# sismin_LC.net
KiCad netlist of a schematic drawn in EAGLE
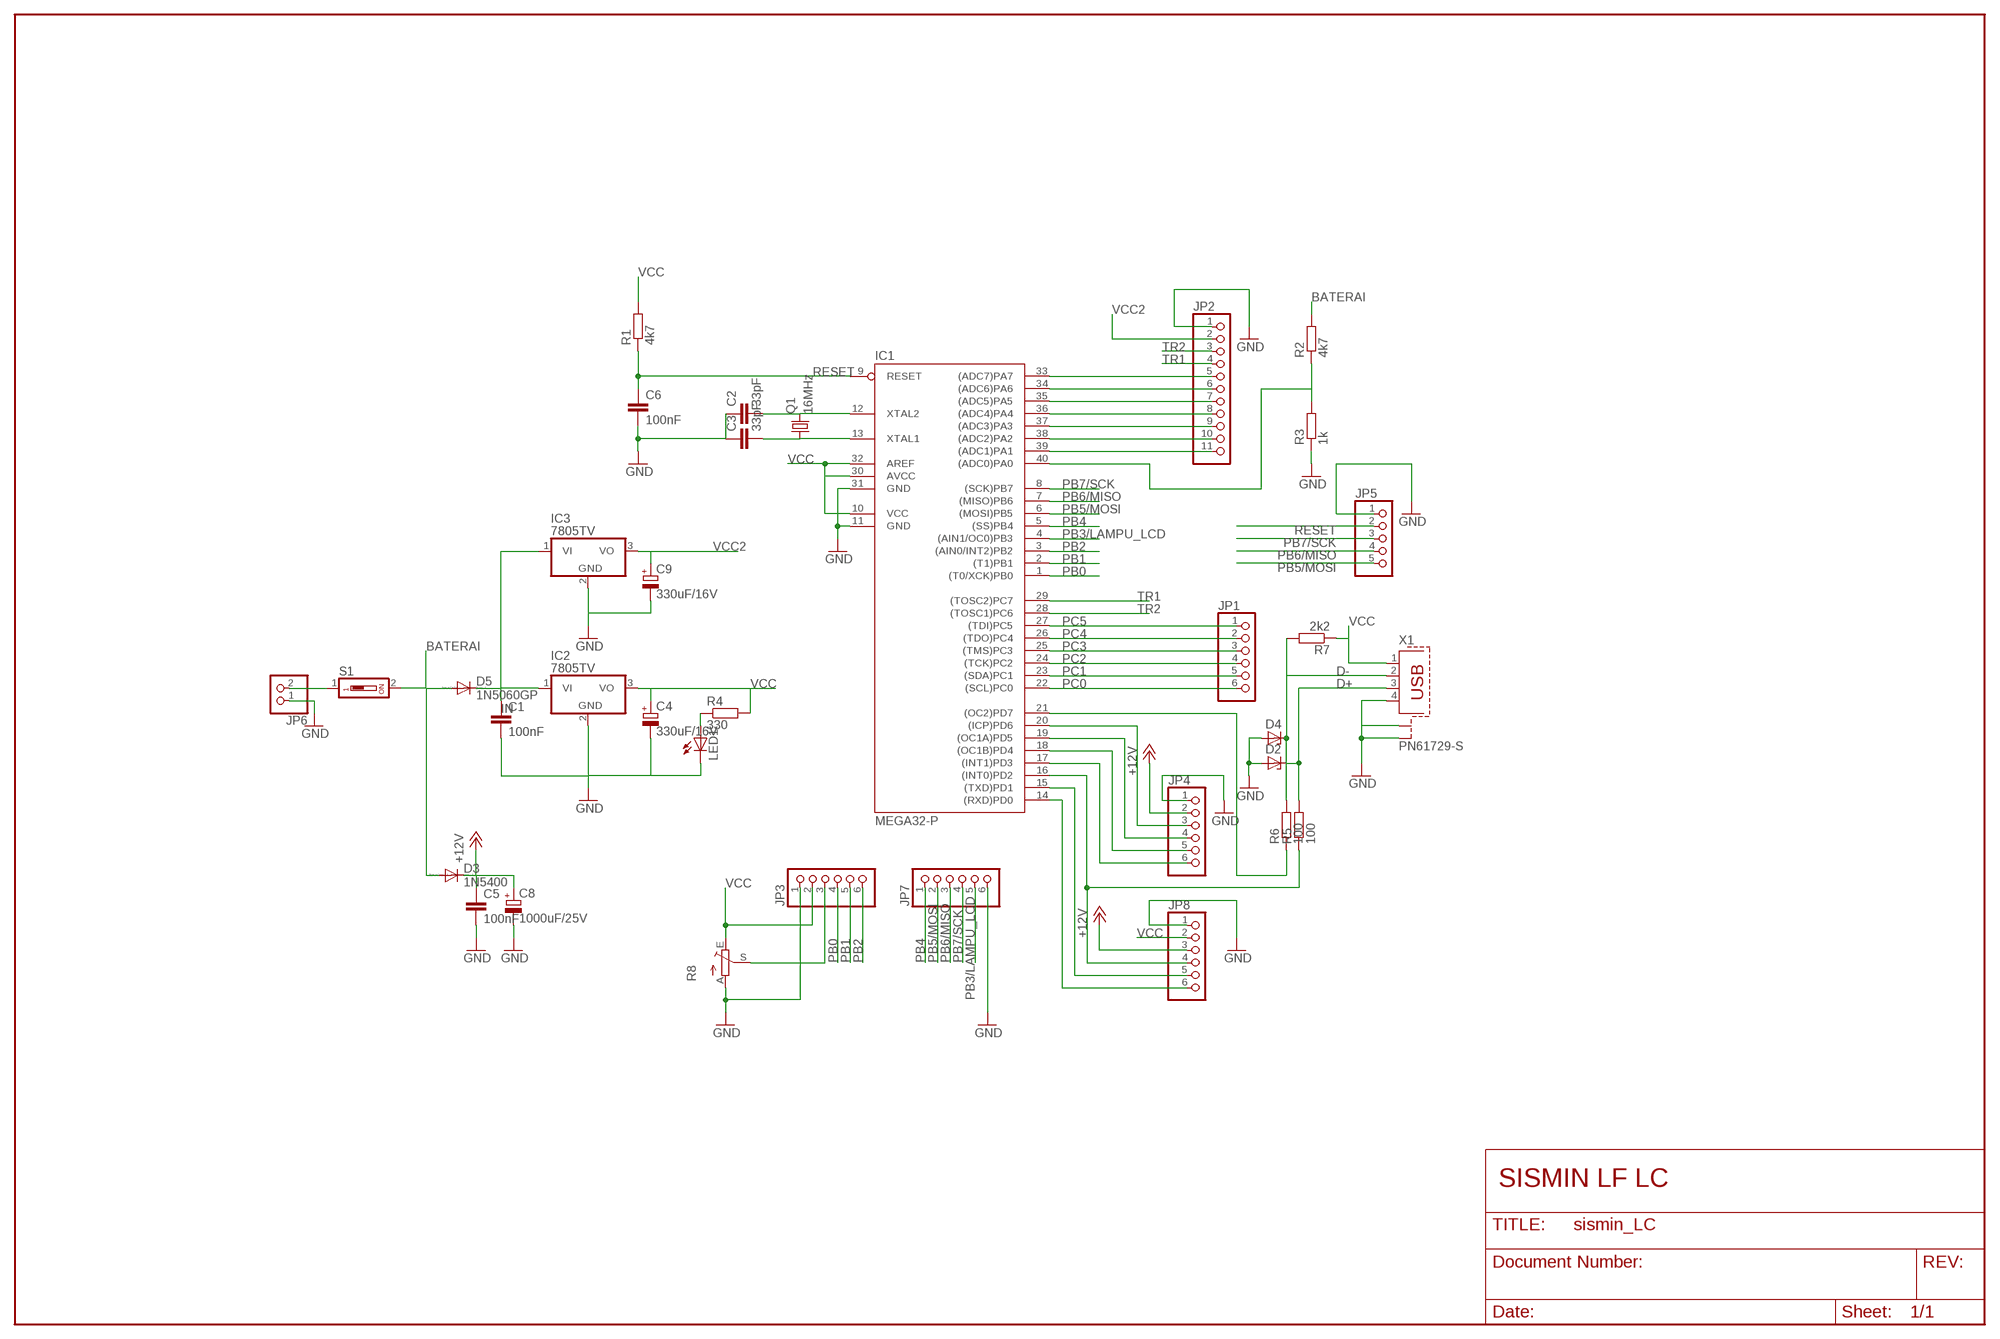
[diagram p0: schematic, sheet 1]

(export (version "E")
  (design (tool "Eeschema 10.0.6"))
  (components
    (comp (ref "C1")
      (value "100nF")
      (footprint "eagle-import:C050-025X075")
      (libsource (lib "eagle-import") (part "C-EU050-025X075"))
    )
    (comp (ref "C2")
      (value "33pF")
      (footprint "eagle-import:C025-025X050")
      (libsource (lib "eagle-import") (part "C-EU025-025X050"))
    )
    (comp (ref "C3")
      (value "33pF")
      (footprint "eagle-import:C025-025X050")
      (libsource (lib "eagle-import") (part "C-EU025-025X050"))
    )
    (comp (ref "C4")
      (value "330uF/16V")
      (footprint "eagle-import:E2-5")
      (libsource (lib "eagle-import") (part "CPOL-EUE2-5"))
    )
    (comp (ref "C5")
      (value "100nF")
      (footprint "eagle-import:C050-025X075")
      (libsource (lib "eagle-import") (part "C-EU050-025X075"))
    )
    (comp (ref "C6")
      (value "100nF")
      (footprint "eagle-import:C050-025X075")
      (libsource (lib "eagle-import") (part "C-EU050-025X075"))
    )
    (comp (ref "C8")
      (value "1000uF/25V")
      (footprint "eagle-import:E2,5-6")
      (libsource (lib "eagle-import") (part "CPOL-EUE2.5-6"))
    )
    (comp (ref "C9")
      (value "330uF/16V")
      (footprint "eagle-import:E2-5")
      (libsource (lib "eagle-import") (part "CPOL-EUE2-5"))
    )
    (comp (ref "D2")
      (value "ZENER-DIODEDO41Z10")
      (footprint "eagle-import:DO41Z10")
      (libsource (lib "eagle-import") (part "ZENER-DIODEDO41Z10"))
    )
    (comp (ref "D3")
      (value "1N5400")
      (footprint "eagle-import:DO201-15")
      (libsource (lib "eagle-import") (part "1N5400"))
    )
    (comp (ref "D4")
      (value "ZENER-DIODEDO41Z10")
      (footprint "eagle-import:DO41Z10")
      (libsource (lib "eagle-import") (part "ZENER-DIODEDO41Z10"))
    )
    (comp (ref "D5")
      (value "1N5060GP")
      (footprint "eagle-import:DO15-12")
      (libsource (lib "eagle-import") (part "1N5060GP"))
    )
    (comp (ref "IC1")
      (value "MEGA32-P")
      (footprint "eagle-import:DIL40")
      (fields (field (name "MPN") "ATMEGA32-16PU"))
      (libsource (lib "eagle-import") (part "MEGA32-P"))
    )
    (comp (ref "IC2")
      (value "7805TV")
      (footprint "eagle-import:TO220V")
      (libsource (lib "eagle-import") (part "78TV05"))
    )
    (comp (ref "IC3")
      (value "7805TV")
      (footprint "eagle-import:TO220V")
      (libsource (lib "eagle-import") (part "78TV05"))
    )
    (comp (ref "JP1")
      (value "PINHD-1X6")
      (footprint "eagle-import:1X06")
      (libsource (lib "eagle-import") (part "PINHD-1X6"))
    )
    (comp (ref "JP2")
      (value "PINHD-1X11")
      (footprint "eagle-import:1X11")
      (libsource (lib "eagle-import") (part "PINHD-1X11"))
    )
    (comp (ref "JP3")
      (value "PINHD-1X6")
      (footprint "eagle-import:1X06")
      (libsource (lib "eagle-import") (part "PINHD-1X6"))
    )
    (comp (ref "JP4")
      (value "PINHD-1X6")
      (footprint "eagle-import:1X06")
      (libsource (lib "eagle-import") (part "PINHD-1X6"))
    )
    (comp (ref "JP5")
      (value "PINHD-1X5")
      (footprint "eagle-import:1X05")
      (libsource (lib "eagle-import") (part "PINHD-1X5"))
    )
    (comp (ref "JP6")
      (value "PINHD-1X2")
      (footprint "eagle-import:1X02")
      (libsource (lib "eagle-import") (part "PINHD-1X2"))
    )
    (comp (ref "JP7")
      (value "PINHD-1X6")
      (footprint "eagle-import:1X06")
      (libsource (lib "eagle-import") (part "PINHD-1X6"))
    )
    (comp (ref "JP8")
      (value "PINHD-1X6")
      (footprint "eagle-import:1X06")
      (libsource (lib "eagle-import") (part "PINHD-1X6"))
    )
    (comp (ref "LED1")
      (value "LED3MM")
      (footprint "eagle-import:LED3MM")
      (libsource (lib "eagle-import") (part "LED3MM"))
    )
    (comp (ref "Q1")
      (value "16MHz")
      (footprint "eagle-import:HC49_S")
      (libsource (lib "eagle-import") (part "CRYSTALHC49S"))
    )
    (comp (ref "R1")
      (value "4k7")
      (footprint "eagle-import:0204_7")
      (libsource (lib "eagle-import") (part "R-EU_0204/7"))
    )
    (comp (ref "R2")
      (value "4k7")
      (footprint "eagle-import:0204_7")
      (libsource (lib "eagle-import") (part "R-EU_0204/7"))
    )
    (comp (ref "R3")
      (value "1k")
      (footprint "eagle-import:0204_7")
      (libsource (lib "eagle-import") (part "R-EU_0204/7"))
    )
    (comp (ref "R4")
      (value "330")
      (footprint "eagle-import:0204_7")
      (libsource (lib "eagle-import") (part "R-EU_0204/7"))
    )
    (comp (ref "R5")
      (value "100")
      (footprint "eagle-import:0204_7")
      (libsource (lib "eagle-import") (part "R-EU_0204/7"))
    )
    (comp (ref "R6")
      (value "100")
      (footprint "eagle-import:0204_7")
      (libsource (lib "eagle-import") (part "R-EU_0204/7"))
    )
    (comp (ref "R7")
      (value "2k2")
      (footprint "eagle-import:0204_7")
      (libsource (lib "eagle-import") (part "R-EU_0204/7"))
    )
    (comp (ref "R8")
      (value "TRIM_EU-RS3")
      (footprint "eagle-import:RS3")
      (libsource (lib "eagle-import") (part "TRIM_EU-RS3"))
    )
    (comp (ref "S1")
      (value "DS01")
      (footprint "eagle-import:DS-01")
      (libsource (lib "eagle-import") (part "DS01"))
    )
    (comp (ref "X1")
      (value "PN61729-S")
      (footprint "eagle-import:PN61729-S")
      (libsource (lib "eagle-import") (part "PN61729-S"))
    )
  )
  (nets
    (net (code "1") (name "+12V") (class "Default")
      (node (ref "C5") (pin "1") (pinfunction "1_1") (pintype "passive"))
      (node (ref "C8") (pin "+") (pinfunction "+_+") (pintype "passive"))
      (node (ref "D3") (pin "C") (pinfunction "C_C") (pintype "passive"))
      (node (ref "JP4") (pin "2") (pinfunction "2_2") (pintype "passive"))
      (node (ref "JP8") (pin "3") (pinfunction "3_3") (pintype "passive"))
    )
    (net (code "2") (name "/BATERAI") (class "Default")
      (node (ref "D3") (pin "A") (pinfunction "A_A") (pintype "passive"))
      (node (ref "D5") (pin "A") (pinfunction "A_A") (pintype "passive"))
      (node (ref "R2") (pin "2") (pinfunction "2_2") (pintype "passive"))
      (node (ref "S1") (pin "2") (pinfunction "2_2") (pintype "passive"))
    )
    (net (code "3") (name "/D+") (class "Default")
      (node (ref "D2") (pin "C") (pinfunction "C_C") (pintype "passive"))
      (node (ref "R5") (pin "2") (pinfunction "2_2") (pintype "passive"))
      (node (ref "X1") (pin "3") (pinfunction "3_3") (pintype "passive"))
    )
    (net (code "4") (name "/D-") (class "Default")
      (node (ref "D4") (pin "C") (pinfunction "C_C") (pintype "passive"))
      (node (ref "R6") (pin "2") (pinfunction "2_2") (pintype "passive"))
      (node (ref "R7") (pin "2") (pinfunction "2_2") (pintype "passive"))
      (node (ref "X1") (pin "2") (pinfunction "2_2") (pintype "passive"))
    )
    (net (code "5") (name "/IN") (class "Default")
      (node (ref "C1") (pin "1") (pinfunction "1_1") (pintype "passive"))
      (node (ref "D5") (pin "C") (pinfunction "C_C") (pintype "passive"))
      (node (ref "IC2") (pin "1") (pinfunction "VI_1") (pintype "input"))
      (node (ref "IC3") (pin "1") (pinfunction "VI_1") (pintype "input"))
    )
    (net (code "6") (name "/PB0") (class "Default")
      (node (ref "IC1") (pin "1") (pinfunction "(T0/XCK)PB0_1") (pintype "bidirectional"))
      (node (ref "JP3") (pin "4") (pinfunction "4_4") (pintype "passive"))
    )
    (net (code "7") (name "/PB1") (class "Default")
      (node (ref "IC1") (pin "2") (pinfunction "(T1)PB1_2") (pintype "bidirectional"))
      (node (ref "JP3") (pin "5") (pinfunction "5_5") (pintype "passive"))
    )
    (net (code "8") (name "/PB2") (class "Default")
      (node (ref "IC1") (pin "3") (pinfunction "(AIN0/INT2)PB2_3") (pintype "bidirectional"))
      (node (ref "JP3") (pin "6") (pinfunction "6_6") (pintype "passive"))
    )
    (net (code "9") (name "/PB3{slash}LAMPU_LCD") (class "Default")
      (node (ref "IC1") (pin "4") (pinfunction "(AIN1/OC0)PB3_4") (pintype "bidirectional"))
      (node (ref "JP7") (pin "5") (pinfunction "5_5") (pintype "passive"))
    )
    (net (code "10") (name "/PB4") (class "Default")
      (node (ref "IC1") (pin "5") (pinfunction "(SS)PB4_5") (pintype "bidirectional"))
      (node (ref "JP7") (pin "1") (pinfunction "1_1") (pintype "passive"))
    )
    (net (code "11") (name "/PB5{slash}MOSI") (class "Default")
      (node (ref "IC1") (pin "6") (pinfunction "(MOSI)PB5_6") (pintype "bidirectional"))
      (node (ref "JP5") (pin "5") (pinfunction "5_5") (pintype "passive"))
      (node (ref "JP7") (pin "2") (pinfunction "2_2") (pintype "passive"))
    )
    (net (code "12") (name "/PB6{slash}MISO") (class "Default")
      (node (ref "IC1") (pin "7") (pinfunction "(MISO)PB6_7") (pintype "bidirectional"))
      (node (ref "JP5") (pin "4") (pinfunction "4_4") (pintype "passive"))
      (node (ref "JP7") (pin "3") (pinfunction "3_3") (pintype "passive"))
    )
    (net (code "13") (name "/PB7{slash}SCK") (class "Default")
      (node (ref "IC1") (pin "8") (pinfunction "(SCK)PB7_8") (pintype "bidirectional"))
      (node (ref "JP5") (pin "3") (pinfunction "3_3") (pintype "passive"))
      (node (ref "JP7") (pin "4") (pinfunction "4_4") (pintype "passive"))
    )
    (net (code "14") (name "/PC0") (class "Default")
      (node (ref "IC1") (pin "22") (pinfunction "(SCL)PC0_22") (pintype "bidirectional"))
      (node (ref "JP1") (pin "6") (pinfunction "6_6") (pintype "passive"))
    )
    (net (code "15") (name "/PC1") (class "Default")
      (node (ref "IC1") (pin "23") (pinfunction "(SDA)PC1_23") (pintype "bidirectional"))
      (node (ref "JP1") (pin "5") (pinfunction "5_5") (pintype "passive"))
    )
    (net (code "16") (name "/PC2") (class "Default")
      (node (ref "IC1") (pin "24") (pinfunction "(TCK)PC2_24") (pintype "bidirectional"))
      (node (ref "JP1") (pin "4") (pinfunction "4_4") (pintype "passive"))
    )
    (net (code "17") (name "/PC3") (class "Default")
      (node (ref "IC1") (pin "25") (pinfunction "(TMS)PC3_25") (pintype "bidirectional"))
      (node (ref "JP1") (pin "3") (pinfunction "3_3") (pintype "passive"))
    )
    (net (code "18") (name "/PC4") (class "Default")
      (node (ref "IC1") (pin "26") (pinfunction "(TDO)PC4_26") (pintype "bidirectional"))
      (node (ref "JP1") (pin "2") (pinfunction "2_2") (pintype "passive"))
    )
    (net (code "19") (name "/PC5") (class "Default")
      (node (ref "IC1") (pin "27") (pinfunction "(TDI)PC5_27") (pintype "bidirectional"))
      (node (ref "JP1") (pin "1") (pinfunction "1_1") (pintype "passive"))
    )
    (net (code "20") (name "/RESET") (class "Default")
      (node (ref "C6") (pin "1") (pinfunction "1_1") (pintype "passive"))
      (node (ref "IC1") (pin "9") (pinfunction "RESET_9") (pintype "input"))
      (node (ref "JP5") (pin "2") (pinfunction "2_2") (pintype "passive"))
      (node (ref "R1") (pin "1") (pinfunction "1_1") (pintype "passive"))
    )
    (net (code "21") (name "/TR1") (class "Default")
      (node (ref "IC1") (pin "29") (pinfunction "(TOSC2)PC7_29") (pintype "bidirectional"))
      (node (ref "JP2") (pin "4") (pinfunction "4_4") (pintype "passive"))
    )
    (net (code "22") (name "/TR2") (class "Default")
      (node (ref "IC1") (pin "28") (pinfunction "(TOSC1)PC6_28") (pintype "bidirectional"))
      (node (ref "JP2") (pin "3") (pinfunction "3_3") (pintype "passive"))
    )
    (net (code "23") (name "/VCC") (class "Default")
      (node (ref "C4") (pin "+") (pinfunction "+_+") (pintype "passive"))
      (node (ref "IC1") (pin "10") (pinfunction "VCC_10") (pintype "power_in"))
      (node (ref "IC1") (pin "30") (pinfunction "AVCC_30") (pintype "power_in"))
      (node (ref "IC1") (pin "32") (pinfunction "AREF_32") (pintype "passive"))
      (node (ref "IC2") (pin "3") (pinfunction "VO_3") (pintype "passive"))
      (node (ref "JP3") (pin "2") (pinfunction "2_2") (pintype "passive"))
      (node (ref "JP8") (pin "2") (pinfunction "2_2") (pintype "passive"))
      (node (ref "R1") (pin "2") (pinfunction "2_2") (pintype "passive"))
      (node (ref "R4") (pin "2") (pinfunction "2_2") (pintype "passive"))
      (node (ref "R7") (pin "1") (pinfunction "1_1") (pintype "passive"))
      (node (ref "R8") (pin "E") (pinfunction "E_E") (pintype "passive"))
      (node (ref "X1") (pin "1") (pinfunction "1_1") (pintype "passive"))
    )
    (net (code "24") (name "/VCC2") (class "Default")
      (node (ref "C9") (pin "+") (pinfunction "+_+") (pintype "passive"))
      (node (ref "IC3") (pin "3") (pinfunction "VO_3") (pintype "passive"))
      (node (ref "JP2") (pin "2") (pinfunction "2_2") (pintype "passive"))
    )
    (net (code "25") (name "GND") (class "Default")
      (node (ref "C1") (pin "2") (pinfunction "2_2") (pintype "passive"))
      (node (ref "C2") (pin "1") (pinfunction "1_1") (pintype "passive"))
      (node (ref "C3") (pin "1") (pinfunction "1_1") (pintype "passive"))
      (node (ref "C4") (pin "-") (pinfunction "-_-") (pintype "passive"))
      (node (ref "C5") (pin "2") (pinfunction "2_2") (pintype "passive"))
      (node (ref "C6") (pin "2") (pinfunction "2_2") (pintype "passive"))
      (node (ref "C8") (pin "-") (pinfunction "-_-") (pintype "passive"))
      (node (ref "C9") (pin "-") (pinfunction "-_-") (pintype "passive"))
      (node (ref "D2") (pin "A") (pinfunction "A_A") (pintype "passive"))
      (node (ref "D4") (pin "A") (pinfunction "A_A") (pintype "passive"))
      (node (ref "IC1") (pin "11") (pinfunction "GND_11") (pintype "power_in"))
      (node (ref "IC1") (pin "31") (pinfunction "GND_31") (pintype "power_in"))
      (node (ref "IC2") (pin "2") (pinfunction "GND_2") (pintype "passive"))
      (node (ref "IC3") (pin "2") (pinfunction "GND_2") (pintype "passive"))
      (node (ref "JP2") (pin "1") (pinfunction "1_1") (pintype "passive"))
      (node (ref "JP3") (pin "1") (pinfunction "1_1") (pintype "passive"))
      (node (ref "JP4") (pin "1") (pinfunction "1_1") (pintype "passive"))
      (node (ref "JP5") (pin "1") (pinfunction "1_1") (pintype "passive"))
      (node (ref "JP6") (pin "1") (pinfunction "1_1") (pintype "passive"))
      (node (ref "JP7") (pin "6") (pinfunction "6_6") (pintype "passive"))
      (node (ref "JP8") (pin "1") (pinfunction "1_1") (pintype "passive"))
      (node (ref "LED1") (pin "K") (pinfunction "C_K") (pintype "passive"))
      (node (ref "R3") (pin "1") (pinfunction "1_1") (pintype "passive"))
      (node (ref "R8") (pin "A") (pinfunction "A_A") (pintype "passive"))
      (node (ref "X1") (pin "4") (pinfunction "4_4") (pintype "passive"))
      (node (ref "X1") (pin "S1") (pinfunction "S1_S1") (pintype "passive"))
      (node (ref "X1") (pin "S2") (pinfunction "S2_S2") (pintype "passive"))
    )
    (net (code "26") (name "Net-(IC1-(ADC0)PA0)") (class "Default")
      (node (ref "IC1") (pin "40") (pinfunction "(ADC0)PA0_40") (pintype "bidirectional"))
      (node (ref "R2") (pin "1") (pinfunction "1_1") (pintype "passive"))
      (node (ref "R3") (pin "2") (pinfunction "2_2") (pintype "passive"))
    )
    (net (code "27") (name "Net-(IC1-(ADC1)PA1)") (class "Default")
      (node (ref "IC1") (pin "39") (pinfunction "(ADC1)PA1_39") (pintype "bidirectional"))
      (node (ref "JP2") (pin "11") (pinfunction "11_11") (pintype "passive"))
    )
    (net (code "28") (name "Net-(IC1-(ADC2)PA2)") (class "Default")
      (node (ref "IC1") (pin "38") (pinfunction "(ADC2)PA2_38") (pintype "bidirectional"))
      (node (ref "JP2") (pin "10") (pinfunction "10_10") (pintype "passive"))
    )
    (net (code "29") (name "Net-(IC1-(ADC3)PA3)") (class "Default")
      (node (ref "IC1") (pin "37") (pinfunction "(ADC3)PA3_37") (pintype "bidirectional"))
      (node (ref "JP2") (pin "9") (pinfunction "9_9") (pintype "passive"))
    )
    (net (code "30") (name "Net-(IC1-(ADC4)PA4)") (class "Default")
      (node (ref "IC1") (pin "36") (pinfunction "(ADC4)PA4_36") (pintype "bidirectional"))
      (node (ref "JP2") (pin "8") (pinfunction "8_8") (pintype "passive"))
    )
    (net (code "31") (name "Net-(IC1-(ADC5)PA5)") (class "Default")
      (node (ref "IC1") (pin "35") (pinfunction "(ADC5)PA5_35") (pintype "bidirectional"))
      (node (ref "JP2") (pin "7") (pinfunction "7_7") (pintype "passive"))
    )
    (net (code "32") (name "Net-(IC1-(ADC6)PA6)") (class "Default")
      (node (ref "IC1") (pin "34") (pinfunction "(ADC6)PA6_34") (pintype "bidirectional"))
      (node (ref "JP2") (pin "6") (pinfunction "6_6") (pintype "passive"))
    )
    (net (code "33") (name "Net-(IC1-(ADC7)PA7)") (class "Default")
      (node (ref "IC1") (pin "33") (pinfunction "(ADC7)PA7_33") (pintype "bidirectional"))
      (node (ref "JP2") (pin "5") (pinfunction "5_5") (pintype "passive"))
    )
    (net (code "34") (name "Net-(IC1-(ICP)PD6)") (class "Default")
      (node (ref "IC1") (pin "20") (pinfunction "(ICP)PD6_20") (pintype "bidirectional"))
      (node (ref "JP4") (pin "3") (pinfunction "3_3") (pintype "passive"))
    )
    (net (code "35") (name "Net-(IC1-(INT0)PD2)") (class "Default")
      (node (ref "IC1") (pin "16") (pinfunction "(INT0)PD2_16") (pintype "bidirectional"))
      (node (ref "JP8") (pin "4") (pinfunction "4_4") (pintype "passive"))
      (node (ref "R5") (pin "1") (pinfunction "1_1") (pintype "passive"))
    )
    (net (code "36") (name "Net-(IC1-(INT1)PD3)") (class "Default")
      (node (ref "IC1") (pin "17") (pinfunction "(INT1)PD3_17") (pintype "bidirectional"))
      (node (ref "JP4") (pin "6") (pinfunction "6_6") (pintype "passive"))
    )
    (net (code "37") (name "Net-(IC1-(OC1A)PD5)") (class "Default")
      (node (ref "IC1") (pin "19") (pinfunction "(OC1A)PD5_19") (pintype "bidirectional"))
      (node (ref "JP4") (pin "4") (pinfunction "4_4") (pintype "passive"))
    )
    (net (code "38") (name "Net-(IC1-(OC1B)PD4)") (class "Default")
      (node (ref "IC1") (pin "18") (pinfunction "(OC1B)PD4_18") (pintype "bidirectional"))
      (node (ref "JP4") (pin "5") (pinfunction "5_5") (pintype "passive"))
    )
    (net (code "39") (name "Net-(IC1-(OC2)PD7)") (class "Default")
      (node (ref "IC1") (pin "21") (pinfunction "(OC2)PD7_21") (pintype "bidirectional"))
      (node (ref "R6") (pin "1") (pinfunction "1_1") (pintype "passive"))
    )
    (net (code "40") (name "Net-(IC1-(RXD)PD0)") (class "Default")
      (node (ref "IC1") (pin "14") (pinfunction "(RXD)PD0_14") (pintype "bidirectional"))
      (node (ref "JP8") (pin "6") (pinfunction "6_6") (pintype "passive"))
    )
    (net (code "41") (name "Net-(IC1-(TXD)PD1)") (class "Default")
      (node (ref "IC1") (pin "15") (pinfunction "(TXD)PD1_15") (pintype "bidirectional"))
      (node (ref "JP8") (pin "5") (pinfunction "5_5") (pintype "passive"))
    )
    (net (code "42") (name "Net-(IC1-XTAL1)") (class "Default")
      (node (ref "C3") (pin "2") (pinfunction "2_2") (pintype "passive"))
      (node (ref "IC1") (pin "13") (pinfunction "XTAL1_13") (pintype "bidirectional"))
      (node (ref "Q1") (pin "1") (pinfunction "1_1") (pintype "passive"))
    )
    (net (code "43") (name "Net-(IC1-XTAL2)") (class "Default")
      (node (ref "C2") (pin "2") (pinfunction "2_2") (pintype "passive"))
      (node (ref "IC1") (pin "12") (pinfunction "XTAL2_12") (pintype "bidirectional"))
      (node (ref "Q1") (pin "2") (pinfunction "2_2") (pintype "passive"))
    )
    (net (code "44") (name "Net-(JP3-Pad3)") (class "Default")
      (node (ref "JP3") (pin "3") (pinfunction "3_3") (pintype "passive"))
      (node (ref "R8") (pin "S") (pinfunction "S_S") (pintype "passive"))
    )
    (net (code "45") (name "Net-(JP6-Pad2)") (class "Default")
      (node (ref "JP6") (pin "2") (pinfunction "2_2") (pintype "passive"))
      (node (ref "S1") (pin "1") (pinfunction "1_1") (pintype "passive"))
    )
    (net (code "46") (name "Net-(LED1-PadA)") (class "Default")
      (node (ref "LED1") (pin "A") (pinfunction "A_A") (pintype "passive"))
      (node (ref "R4") (pin "1") (pinfunction "1_1") (pintype "passive"))
    )
  )
)
